# Terminierung_RS485-005.net
KiCad netlist of a schematic drawn in EAGLE
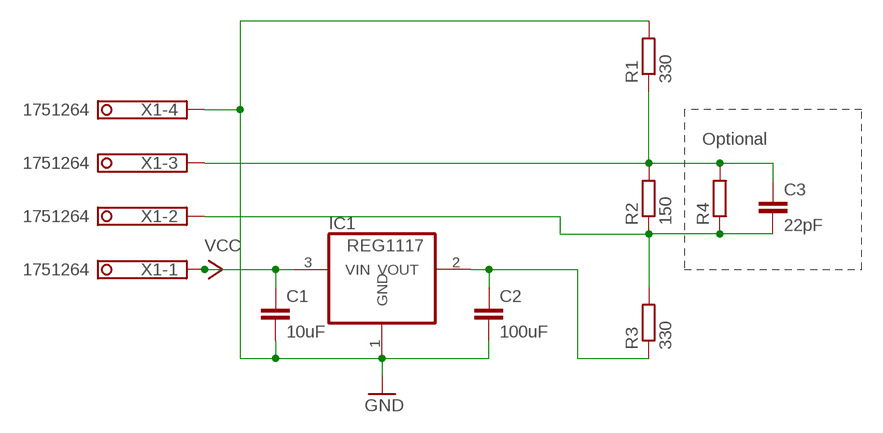
[diagram p0: schematic, sheet 1]

(export (version "E")
  (design (tool "Eeschema 10.0.6"))
  (components
    (comp (ref "C1")
      (value "10uF")
      (footprint "eagle-import:C0805K")
      (libsource (lib "eagle-import") (part "C-EUC0805K"))
    )
    (comp (ref "C2")
      (value "100uF")
      (footprint "eagle-import:C0805K")
      (libsource (lib "eagle-import") (part "C-EUC0805K"))
    )
    (comp (ref "C3")
      (value "22pF")
      (footprint "eagle-import:C0805K")
      (libsource (lib "eagle-import") (part "C-EUC0805K"))
    )
    (comp (ref "IC1")
      (value "REG1117")
      (footprint "eagle-import:SOT223")
      (libsource (lib "eagle-import") (part "REG1117"))
    )
    (comp (ref "R1")
      (value "330")
      (footprint "eagle-import:R0805")
      (libsource (lib "eagle-import") (part "R-EU_R0805"))
    )
    (comp (ref "R2")
      (value "150")
      (footprint "eagle-import:R0805")
      (libsource (lib "eagle-import") (part "R-EU_R0805"))
    )
    (comp (ref "R3")
      (value "330")
      (footprint "eagle-import:R0805")
      (libsource (lib "eagle-import") (part "R-EU_R0805"))
    )
    (comp (ref "R4")
      (value "R-EU_M1206")
      (footprint "eagle-import:M1206")
      (libsource (lib "eagle-import") (part "R-EU_M1206"))
    )
    (comp (ref "X1")
      (value "1751264")
      (footprint "eagle-import:1751264")
      (fields (field (name "MF") "VIN"))
      (libsource (lib "eagle-import") (part "1751264"))
    )
  )
  (nets
    (net (code "1") (name "GND") (class "Default")
      (node (ref "C1") (pin "2") (pinfunction "2_2") (pintype "passive"))
      (node (ref "C2") (pin "2") (pinfunction "2_2") (pintype "passive"))
      (node (ref "IC1") (pin "1") (pinfunction "GND_1") (pintype "power_in"))
      (node (ref "R1") (pin "2") (pinfunction "2_2") (pintype "passive"))
      (node (ref "X1") (pin "4") (pinfunction "K_4") (pintype "passive"))
    )
    (net (code "2") (name "Net-(IC1-VOUT)") (class "Default")
      (node (ref "C2") (pin "1") (pinfunction "1_1") (pintype "passive"))
      (node (ref "IC1") (pin "2") (pinfunction "VOUT_2") (pintype "output"))
      (node (ref "R3") (pin "1") (pinfunction "1_1") (pintype "passive"))
    )
    (net (code "3") (name "Net-(X1B-K)") (class "Default")
      (node (ref "C3") (pin "2") (pinfunction "2_2") (pintype "passive"))
      (node (ref "R2") (pin "1") (pinfunction "1_1") (pintype "passive"))
      (node (ref "R3") (pin "2") (pinfunction "2_2") (pintype "passive"))
      (node (ref "R4") (pin "1") (pinfunction "1_1") (pintype "passive"))
      (node (ref "X1") (pin "2") (pinfunction "K_2") (pintype "passive"))
    )
    (net (code "4") (name "Net-(X1C-K)") (class "Default")
      (node (ref "C3") (pin "1") (pinfunction "1_1") (pintype "passive"))
      (node (ref "R1") (pin "1") (pinfunction "1_1") (pintype "passive"))
      (node (ref "R2") (pin "2") (pinfunction "2_2") (pintype "passive"))
      (node (ref "R4") (pin "2") (pinfunction "2_2") (pintype "passive"))
      (node (ref "X1") (pin "3") (pinfunction "K_3") (pintype "passive"))
    )
    (net (code "5") (name "VCC") (class "Default")
      (node (ref "C1") (pin "1") (pinfunction "1_1") (pintype "passive"))
      (node (ref "IC1") (pin "3") (pinfunction "VIN_3") (pintype "input"))
      (node (ref "X1") (pin "1") (pinfunction "K_1") (pintype "passive"))
    )
  )
)
